# BW1092_USB.net
KiCad netlist of a schematic drawn in Altium Designer
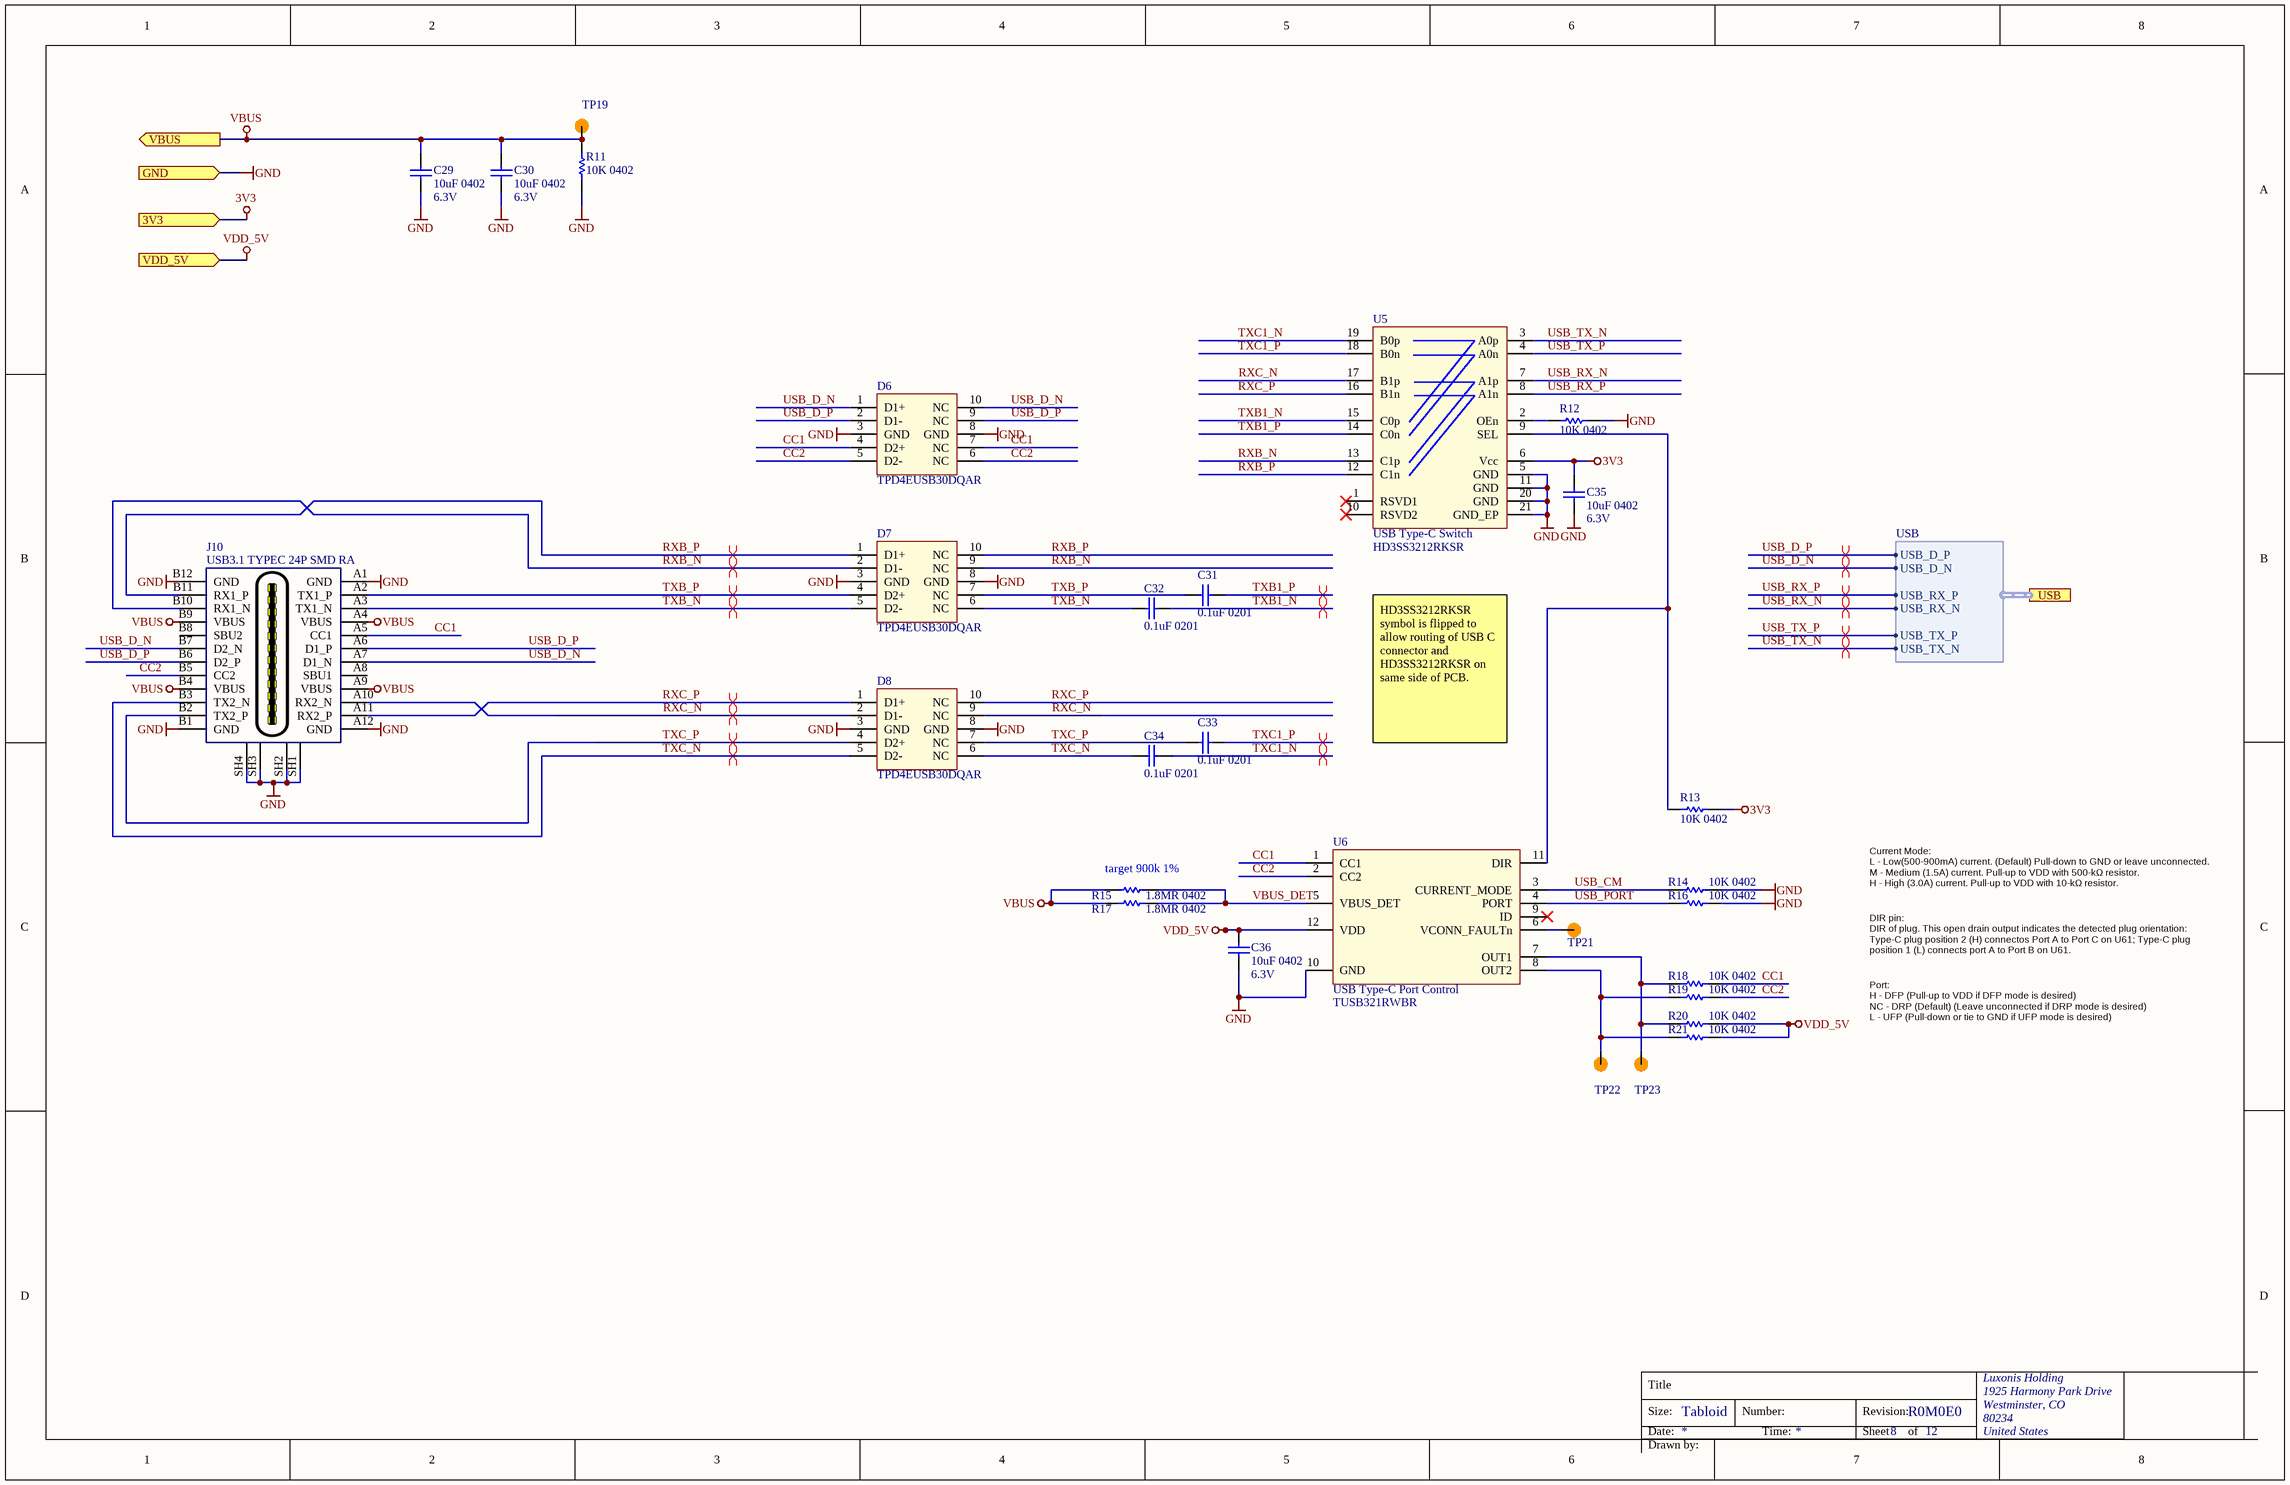
[diagram p0: BW1092_USB.SchDoc]

(export (version "E")
  (design (tool "Eeschema 10.0.6"))
  (components
    (comp (ref "C29")
      (value "10uF 0402")
      (footprint "CAP_Altium_Vault_Generic:CAPC0402(1005)70_L")
      (description "CAP CER 10UF 6.3V X5R 0402 20%")
      (fields (field (name "TOLERANCE") "20%") (field (name "VOLTAGE RATING") "6.3V"))
      (libsource (lib "LuxonisMaster") (part "GRM155R60J106ME15D"))
    )
    (comp (ref "C30")
      (value "10uF 0402")
      (footprint "CAP_Altium_Vault_Generic:CAPC0402(1005)70_L")
      (description "CAP CER 10UF 6.3V X5R 0402 20%")
      (fields (field (name "TOLERANCE") "20%") (field (name "VOLTAGE RATING") "6.3V"))
      (libsource (lib "LuxonisMaster") (part "GRM155R60J106ME15D"))
    )
    (comp (ref "C31")
      (value "0.1uF 0201")
      (footprint "CAP_Altium_Vault_Generic:CAPC0201(0603)33_L")
      (description "CAP CER 0.1UF 10V X5R 0201")
      (fields (field (name "TOLERANCE") "10%") (field (name "VOLTAGE") "10V"))
      (libsource (lib "LuxonisMaster") (part "GRM033R61A104KE15D"))
    )
    (comp (ref "C32")
      (value "0.1uF 0201")
      (footprint "CAP_Altium_Vault_Generic:CAPC0201(0603)33_L")
      (description "CAP CER 0.1UF 10V X5R 0201")
      (fields (field (name "TOLERANCE") "10%") (field (name "VOLTAGE") "10V"))
      (libsource (lib "LuxonisMaster") (part "GRM033R61A104KE15D"))
    )
    (comp (ref "C33")
      (value "0.1uF 0201")
      (footprint "CAP_Altium_Vault_Generic:CAPC0201(0603)33_L")
      (description "CAP CER 0.1UF 10V X5R 0201")
      (fields (field (name "TOLERANCE") "10%") (field (name "VOLTAGE") "10V"))
      (libsource (lib "LuxonisMaster") (part "GRM033R61A104KE15D"))
    )
    (comp (ref "C34")
      (value "0.1uF 0201")
      (footprint "CAP_Altium_Vault_Generic:CAPC0201(0603)33_L")
      (description "CAP CER 0.1UF 10V X5R 0201")
      (fields (field (name "TOLERANCE") "10%") (field (name "VOLTAGE") "10V"))
      (libsource (lib "LuxonisMaster") (part "GRM033R61A104KE15D"))
    )
    (comp (ref "C35")
      (value "10uF 0402")
      (footprint "CAP_Altium_Vault_Generic:CAPC0402(1005)70_L")
      (description "CAP CER 10UF 6.3V X5R 0402 20%")
      (fields (field (name "TOLERANCE") "20%") (field (name "VOLTAGE RATING") "6.3V"))
      (libsource (lib "LuxonisMaster") (part "GRM155R60J106ME15D"))
    )
    (comp (ref "C36")
      (value "10uF 0402")
      (footprint "CAP_Altium_Vault_Generic:CAPC0402(1005)70_L")
      (description "CAP CER 10UF 6.3V X5R 0402 20%")
      (fields (field (name "TOLERANCE") "20%") (field (name "VOLTAGE RATING") "6.3V"))
      (libsource (lib "LuxonisMaster") (part "GRM155R60J106ME15D"))
    )
    (comp (ref "D6")
      (value "TPD4EUSB30DQAR")
      (footprint "LuxonisMaster:TPD4EUSB30DQAR")
      (description "TVS DIODE 5.5V 8V 10SON 8V Clamp 1A (8/20µs) Ipp Tvs Diode Surface Mount 10-USON (2.5x1)")
      (libsource (lib "LuxonisMaster") (part "TPD4EUSB30DQAR"))
    )
    (comp (ref "D7")
      (value "TPD4EUSB30DQAR")
      (footprint "LuxonisMaster:TPD4EUSB30DQAR")
      (description "TVS DIODE 5.5V 8V 10SON 8V Clamp 1A (8/20µs) Ipp Tvs Diode Surface Mount 10-USON (2.5x1)")
      (libsource (lib "LuxonisMaster") (part "TPD4EUSB30DQAR"))
    )
    (comp (ref "D8")
      (value "TPD4EUSB30DQAR")
      (footprint "LuxonisMaster:TPD4EUSB30DQAR")
      (description "TVS DIODE 5.5V 8V 10SON 8V Clamp 1A (8/20µs) Ipp Tvs Diode Surface Mount 10-USON (2.5x1)")
      (libsource (lib "LuxonisMaster") (part "TPD4EUSB30DQAR"))
    )
    (comp (ref "J10")
      (value "USB3.1 TYPEC 24P SMD RA")
      (footprint "LuxonisMaster:105450-0101")
      (description "CONN RCP USB3.1 TYPEC 24P SMD RA")
      (libsource (lib "LuxonisMaster") (part "105450-0101"))
    )
    (comp (ref "R11")
      (value "10K 0402")
      (footprint "RES_Altium_Vault_Generic:RESC0402(1005)_L")
      (fields (field (name "TOLERANCE") "1%"))
      (libsource (lib "LuxonisMaster") (part "RC0402FR-1310KL"))
    )
    (comp (ref "R12")
      (value "10K 0402")
      (footprint "RES_Altium_Vault_Generic:RESC0402(1005)_L")
      (fields (field (name "TOLERANCE") "1%"))
      (libsource (lib "LuxonisMaster") (part "RC0402FR-1310KL"))
    )
    (comp (ref "R13")
      (value "10K 0402")
      (footprint "RES_Altium_Vault_Generic:RESC0402(1005)_L")
      (fields (field (name "TOLERANCE") "1%"))
      (libsource (lib "LuxonisMaster") (part "RC0402FR-1310KL"))
    )
    (comp (ref "R14")
      (value "10K 0402")
      (footprint "RES_Altium_Vault_Generic:RESC0402(1005)_L")
      (fields (field (name "TOLERANCE") "1%"))
      (libsource (lib "LuxonisMaster") (part "RC0402FR-1310KL"))
    )
    (comp (ref "R15")
      (value "1.8MR 0402")
      (footprint "RES_Altium_Vault_Generic:RESC0402(1005)_L")
      (description "RES SMD 1.8M OHM 1% 1/16W 0402")
      (fields (field (name "TOLERANCE") "1%"))
      (libsource (lib "LuxonisMaster") (part "CRCW04021M80FKED"))
    )
    (comp (ref "R16")
      (value "10K 0402")
      (footprint "RES_Altium_Vault_Generic:RESC0402(1005)_L")
      (fields (field (name "TOLERANCE") "1%"))
      (libsource (lib "LuxonisMaster") (part "RC0402FR-1310KL"))
    )
    (comp (ref "R17")
      (value "1.8MR 0402")
      (footprint "RES_Altium_Vault_Generic:RESC0402(1005)_L")
      (description "RES SMD 1.8M OHM 1% 1/16W 0402")
      (fields (field (name "TOLERANCE") "1%"))
      (libsource (lib "LuxonisMaster") (part "CRCW04021M80FKED"))
    )
    (comp (ref "R18")
      (value "10K 0402")
      (footprint "RES_Altium_Vault_Generic:RESC0402(1005)_L")
      (fields (field (name "TOLERANCE") "1%"))
      (libsource (lib "LuxonisMaster") (part "RC0402FR-1310KL"))
    )
    (comp (ref "R19")
      (value "10K 0402")
      (footprint "RES_Altium_Vault_Generic:RESC0402(1005)_L")
      (fields (field (name "TOLERANCE") "1%"))
      (libsource (lib "LuxonisMaster") (part "RC0402FR-1310KL"))
    )
    (comp (ref "R20")
      (value "10K 0402")
      (footprint "RES_Altium_Vault_Generic:RESC0402(1005)_L")
      (fields (field (name "TOLERANCE") "1%"))
      (libsource (lib "LuxonisMaster") (part "RC0402FR-1310KL"))
    )
    (comp (ref "R21")
      (value "10K 0402")
      (footprint "RES_Altium_Vault_Generic:RESC0402(1005)_L")
      (fields (field (name "TOLERANCE") "1%"))
      (libsource (lib "LuxonisMaster") (part "RC0402FR-1310KL"))
    )
    (comp (ref "TP19")
      (value "TP100_200_NS")
      (footprint "LuxonisMaster:TP100_200_NS")
      (libsource (lib "LuxonisMaster") (part "TEST_POINT"))
    )
    (comp (ref "TP21")
      (value "TP075_150_NS")
      (footprint "LuxonisMaster:TP075_150_NS")
      (libsource (lib "LuxonisMaster") (part "TEST_POINT"))
    )
    (comp (ref "TP22")
      (value "TP075_150_NS")
      (footprint "LuxonisMaster:TP075_150_NS")
      (libsource (lib "LuxonisMaster") (part "TEST_POINT"))
    )
    (comp (ref "TP23")
      (value "TP075_150_NS")
      (footprint "LuxonisMaster:TP075_150_NS")
      (libsource (lib "LuxonisMaster") (part "TEST_POINT"))
    )
    (comp (ref "U5")
      (value "USB Type-C Switch")
      (footprint "LuxonisMaster:HD3SS3212RKSR")
      (description "IC MUX 2:1 8 OHM 20VQFN")
      (fields (field (name "MANUFACTURER PART NUMBER 1") "HD3SS3212RKSR"))
      (libsource (lib "LuxonisMaster") (part "HD3SS3212RKSR"))
    )
    (comp (ref "U6")
      (value "USB Type-C Port Control")
      (footprint "LuxonisMaster:TUSB321RWBR")
      (description "IC USB PORT CONTROL TYPE-C 12X2Q")
      (fields (field (name "MANUFACTURER PART NUMBER 1") "TUSB321RWBR"))
      (libsource (lib "LuxonisMaster") (part "TUSB321RWBR"))
    )
  )
  (nets
    (net (code "2") (name "/CC1") (class "Default")
      (node (ref "D6") (pin "4") (pinfunction "D2+_4") (pintype "passive"))
      (node (ref "D6") (pin "7") (pinfunction "NC_7") (pintype "passive"))
      (node (ref "J10") (pin "A5") (pinfunction "CC1_A5") (pintype "passive"))
      (node (ref "R18") (pin "2") (pinfunction "2_2") (pintype "passive"))
      (node (ref "U6") (pin "1") (pinfunction "CC1_1") (pintype "passive"))
    )
    (net (code "3") (name "/CC2") (class "Default")
      (node (ref "D6") (pin "5") (pinfunction "D2-_5") (pintype "passive"))
      (node (ref "D6") (pin "6") (pinfunction "NC_6") (pintype "passive"))
      (node (ref "J10") (pin "B5") (pinfunction "CC2_B5") (pintype "passive"))
      (node (ref "R19") (pin "2") (pinfunction "2_2") (pintype "passive"))
      (node (ref "U6") (pin "2") (pinfunction "CC2_2") (pintype "passive"))
    )
    (net (code "4") (name "/RXB_N") (class "Default")
      (node (ref "D7") (pin "2") (pinfunction "D1-_2") (pintype "passive"))
      (node (ref "D7") (pin "9") (pinfunction "NC_9") (pintype "passive"))
      (node (ref "J10") (pin "B10") (pinfunction "RX1_N_B10") (pintype "passive"))
      (node (ref "U5") (pin "13") (pinfunction "C1p_13") (pintype "passive"))
    )
    (net (code "5") (name "/RXB_P") (class "Default")
      (node (ref "D7") (pin "1") (pinfunction "D1+_1") (pintype "passive"))
      (node (ref "D7") (pin "10") (pinfunction "NC_10") (pintype "passive"))
      (node (ref "J10") (pin "B11") (pinfunction "RX1_P_B11") (pintype "passive"))
      (node (ref "U5") (pin "12") (pinfunction "C1n_12") (pintype "passive"))
    )
    (net (code "6") (name "/RXC_N") (class "Default")
      (node (ref "D8") (pin "2") (pinfunction "D1-_2") (pintype "passive"))
      (node (ref "D8") (pin "9") (pinfunction "NC_9") (pintype "passive"))
      (node (ref "J10") (pin "A10") (pinfunction "RX2_N_A10") (pintype "passive"))
      (node (ref "U5") (pin "17") (pinfunction "B1p_17") (pintype "passive"))
    )
    (net (code "7") (name "/RXC_P") (class "Default")
      (node (ref "D8") (pin "1") (pinfunction "D1+_1") (pintype "passive"))
      (node (ref "D8") (pin "10") (pinfunction "NC_10") (pintype "passive"))
      (node (ref "J10") (pin "A11") (pinfunction "RX2_P_A11") (pintype "passive"))
      (node (ref "U5") (pin "16") (pinfunction "B1n_16") (pintype "passive"))
    )
    (net (code "8") (name "/TXB1_N") (class "Default")
      (node (ref "C32") (pin "2") (pinfunction "2_2") (pintype "passive"))
      (node (ref "U5") (pin "15") (pinfunction "C0p_15") (pintype "passive"))
    )
    (net (code "9") (name "/TXB1_P") (class "Default")
      (node (ref "C31") (pin "2") (pinfunction "2_2") (pintype "passive"))
      (node (ref "U5") (pin "14") (pinfunction "C0n_14") (pintype "passive"))
    )
    (net (code "10") (name "/TXB_N") (class "Default")
      (node (ref "C32") (pin "1") (pinfunction "1_1") (pintype "passive"))
      (node (ref "D7") (pin "5") (pinfunction "D2-_5") (pintype "passive"))
      (node (ref "D7") (pin "6") (pinfunction "NC_6") (pintype "passive"))
      (node (ref "J10") (pin "A3") (pinfunction "TX1_N_A3") (pintype "passive"))
    )
    (net (code "11") (name "/TXB_P") (class "Default")
      (node (ref "C31") (pin "1") (pinfunction "1_1") (pintype "passive"))
      (node (ref "D7") (pin "4") (pinfunction "D2+_4") (pintype "passive"))
      (node (ref "D7") (pin "7") (pinfunction "NC_7") (pintype "passive"))
      (node (ref "J10") (pin "A2") (pinfunction "TX1_P_A2") (pintype "passive"))
    )
    (net (code "12") (name "/TXC1_N") (class "Default")
      (node (ref "C34") (pin "2") (pinfunction "2_2") (pintype "passive"))
      (node (ref "U5") (pin "19") (pinfunction "B0p_19") (pintype "passive"))
    )
    (net (code "13") (name "/TXC1_P") (class "Default")
      (node (ref "C33") (pin "2") (pinfunction "2_2") (pintype "passive"))
      (node (ref "U5") (pin "18") (pinfunction "B0n_18") (pintype "passive"))
    )
    (net (code "14") (name "/TXC_N") (class "Default")
      (node (ref "C34") (pin "1") (pinfunction "1_1") (pintype "passive"))
      (node (ref "D8") (pin "5") (pinfunction "D2-_5") (pintype "passive"))
      (node (ref "D8") (pin "6") (pinfunction "NC_6") (pintype "passive"))
      (node (ref "J10") (pin "B3") (pinfunction "TX2_N_B3") (pintype "passive"))
    )
    (net (code "15") (name "/TXC_P") (class "Default")
      (node (ref "C33") (pin "1") (pinfunction "1_1") (pintype "passive"))
      (node (ref "D8") (pin "4") (pinfunction "D2+_4") (pintype "passive"))
      (node (ref "D8") (pin "7") (pinfunction "NC_7") (pintype "passive"))
      (node (ref "J10") (pin "B2") (pinfunction "TX2_P_B2") (pintype "passive"))
    )
    (net (code "16") (name "/USB_CM") (class "Default")
      (node (ref "R14") (pin "1") (pinfunction "1_1") (pintype "passive"))
      (node (ref "U6") (pin "3") (pinfunction "CURRENT_MODE_3") (pintype "passive"))
    )
    (net (code "17") (name "/USB_D_N") (class "Default")
      (node (ref "D6") (pin "1") (pinfunction "D1+_1") (pintype "passive"))
      (node (ref "D6") (pin "10") (pinfunction "NC_10") (pintype "passive"))
      (node (ref "J10") (pin "A7") (pinfunction "D1_N_A7") (pintype "passive"))
      (node (ref "J10") (pin "B7") (pinfunction "D2_N_B7") (pintype "passive"))
    )
    (net (code "18") (name "/USB_D_P") (class "Default")
      (node (ref "D6") (pin "2") (pinfunction "D1-_2") (pintype "passive"))
      (node (ref "D6") (pin "9") (pinfunction "NC_9") (pintype "passive"))
      (node (ref "J10") (pin "A6") (pinfunction "D1_P_A6") (pintype "passive"))
      (node (ref "J10") (pin "B6") (pinfunction "D2_P_B6") (pintype "passive"))
    )
    (net (code "19") (name "/USB_PORT") (class "Default")
      (node (ref "R16") (pin "1") (pinfunction "1_1") (pintype "passive"))
      (node (ref "U6") (pin "4") (pinfunction "PORT_4") (pintype "passive"))
    )
    (net (code "20") (name "/USB_RX_N") (class "Default")
      (node (ref "U5") (pin "7") (pinfunction "A1p_7") (pintype "passive"))
    )
    (net (code "21") (name "/USB_RX_P") (class "Default")
      (node (ref "U5") (pin "8") (pinfunction "A1n_8") (pintype "passive"))
    )
    (net (code "22") (name "/USB_TX_N") (class "Default")
      (node (ref "U5") (pin "3") (pinfunction "A0p_3") (pintype "passive"))
    )
    (net (code "23") (name "/USB_TX_P") (class "Default")
      (node (ref "U5") (pin "4") (pinfunction "A0n_4") (pintype "passive"))
    )
    (net (code "24") (name "/VBUS_DET") (class "Default")
      (node (ref "R15") (pin "2") (pinfunction "2_2") (pintype "passive"))
      (node (ref "R17") (pin "2") (pinfunction "2_2") (pintype "passive"))
      (node (ref "U6") (pin "5") (pinfunction "VBUS_DET_5") (pintype "passive"))
    )
    (net (code "26") (name "3V3") (class "Default")
      (node (ref "C35") (pin "2") (pinfunction "2_2") (pintype "passive"))
      (node (ref "R13") (pin "2") (pinfunction "2_2") (pintype "passive"))
      (node (ref "U5") (pin "6") (pinfunction "Vcc_6") (pintype "passive"))
    )
    (net (code "27") (name "GND") (class "Default")
      (node (ref "C29") (pin "1") (pinfunction "1_1") (pintype "passive"))
      (node (ref "C30") (pin "1") (pinfunction "1_1") (pintype "passive"))
      (node (ref "C35") (pin "1") (pinfunction "1_1") (pintype "passive"))
      (node (ref "C36") (pin "1") (pinfunction "1_1") (pintype "passive"))
      (node (ref "D6") (pin "3") (pinfunction "GND_3") (pintype "passive"))
      (node (ref "D6") (pin "8") (pinfunction "GND_8") (pintype "passive"))
      (node (ref "D7") (pin "3") (pinfunction "GND_3") (pintype "passive"))
      (node (ref "D7") (pin "8") (pinfunction "GND_8") (pintype "passive"))
      (node (ref "D8") (pin "3") (pinfunction "GND_3") (pintype "passive"))
      (node (ref "D8") (pin "8") (pinfunction "GND_8") (pintype "passive"))
      (node (ref "J10") (pin "A1") (pinfunction "GND_A1") (pintype "passive"))
      (node (ref "J10") (pin "A12") (pinfunction "GND_A12") (pintype "passive"))
      (node (ref "J10") (pin "B1") (pinfunction "GND_B1") (pintype "passive"))
      (node (ref "J10") (pin "B12") (pinfunction "GND_B12") (pintype "passive"))
      (node (ref "J10") (pin "SH1") (pinfunction "SH_SH1") (pintype "passive"))
      (node (ref "J10") (pin "SH2") (pinfunction "SH_SH2") (pintype "passive"))
      (node (ref "J10") (pin "SH3") (pinfunction "SH_SH3") (pintype "passive"))
      (node (ref "J10") (pin "SH4") (pinfunction "SH_SH4") (pintype "passive"))
      (node (ref "R11") (pin "1") (pinfunction "1_1") (pintype "passive"))
      (node (ref "R12") (pin "2") (pinfunction "2_2") (pintype "passive"))
      (node (ref "R14") (pin "2") (pinfunction "2_2") (pintype "passive"))
      (node (ref "R16") (pin "2") (pinfunction "2_2") (pintype "passive"))
      (node (ref "U5") (pin "11") (pinfunction "GND_11") (pintype "passive"))
      (node (ref "U5") (pin "20") (pinfunction "GND_20") (pintype "passive"))
      (node (ref "U5") (pin "21") (pinfunction "GND_EP_21") (pintype "passive"))
      (node (ref "U5") (pin "5") (pinfunction "GND_5") (pintype "passive"))
      (node (ref "U6") (pin "10") (pinfunction "GND_10") (pintype "passive"))
    )
    (net (code "28") (name "Net-(U5-OEn)") (class "Default")
      (node (ref "R12") (pin "1") (pinfunction "1_1") (pintype "passive"))
      (node (ref "U5") (pin "2") (pinfunction "OEn_2") (pintype "passive"))
    )
    (net (code "29") (name "Net-(U5-SEL)") (class "Default")
      (node (ref "R13") (pin "1") (pinfunction "1_1") (pintype "passive"))
      (node (ref "U5") (pin "9") (pinfunction "SEL_9") (pintype "passive"))
      (node (ref "U6") (pin "11") (pinfunction "DIR_11") (pintype "passive"))
    )
    (net (code "30") (name "Net-(U6-OUT1)") (class "Default")
      (node (ref "R18") (pin "1") (pinfunction "1_1") (pintype "passive"))
      (node (ref "R20") (pin "1") (pinfunction "1_1") (pintype "passive"))
      (node (ref "TP23") (pin "1") (pintype "passive"))
      (node (ref "U6") (pin "7") (pinfunction "OUT1_7") (pintype "passive"))
    )
    (net (code "31") (name "Net-(U6-OUT2)") (class "Default")
      (node (ref "R19") (pin "1") (pinfunction "1_1") (pintype "passive"))
      (node (ref "R21") (pin "1") (pinfunction "1_1") (pintype "passive"))
      (node (ref "TP22") (pin "1") (pintype "passive"))
      (node (ref "U6") (pin "8") (pinfunction "OUT2_8") (pintype "passive"))
    )
    (net (code "32") (name "Net-(U6-VCONN_FAULTn)") (class "Default")
      (node (ref "TP21") (pin "1") (pintype "passive"))
      (node (ref "U6") (pin "6") (pinfunction "VCONN_FAULTn_6") (pintype "passive"))
    )
    (net (code "33") (name "VBUS") (class "Default")
      (node (ref "C29") (pin "2") (pinfunction "2_2") (pintype "passive"))
      (node (ref "C30") (pin "2") (pinfunction "2_2") (pintype "passive"))
      (node (ref "J10") (pin "A4") (pinfunction "VBUS_A4") (pintype "passive"))
      (node (ref "J10") (pin "A9") (pinfunction "VBUS_A9") (pintype "passive"))
      (node (ref "J10") (pin "B4") (pinfunction "VBUS_B4") (pintype "passive"))
      (node (ref "J10") (pin "B9") (pinfunction "VBUS_B9") (pintype "passive"))
      (node (ref "R11") (pin "2") (pinfunction "2_2") (pintype "passive"))
      (node (ref "R15") (pin "1") (pinfunction "1_1") (pintype "passive"))
      (node (ref "R17") (pin "1") (pinfunction "1_1") (pintype "passive"))
      (node (ref "TP19") (pin "1") (pintype "passive"))
    )
    (net (code "34") (name "VDD_5V") (class "Default")
      (node (ref "C36") (pin "2") (pinfunction "2_2") (pintype "passive"))
      (node (ref "R20") (pin "2") (pinfunction "2_2") (pintype "passive"))
      (node (ref "R21") (pin "2") (pinfunction "2_2") (pintype "passive"))
      (node (ref "U6") (pin "12") (pinfunction "VDD_12") (pintype "passive"))
    )
    (net (code "35") (name "unconnected-(J10-SBU1-PadA8)") (class "Default")
      (node (ref "J10") (pin "A8") (pinfunction "SBU1_A8") (pintype "passive"))
    )
    (net (code "36") (name "unconnected-(J10-SBU2-PadB8)") (class "Default")
      (node (ref "J10") (pin "B8") (pinfunction "SBU2_B8") (pintype "passive"))
    )
    (net (code "37") (name "unconnected-(U5-RSVD1-Pad1)") (class "Default")
      (node (ref "U5") (pin "1") (pinfunction "RSVD1_1") (pintype "passive+no_connect"))
    )
    (net (code "38") (name "unconnected-(U5-RSVD2-Pad10)") (class "Default")
      (node (ref "U5") (pin "10") (pinfunction "RSVD2_10") (pintype "passive+no_connect"))
    )
    (net (code "39") (name "unconnected-(U6-ID-Pad9)") (class "Default")
      (node (ref "U6") (pin "9") (pinfunction "ID_9") (pintype "passive+no_connect"))
    )
  )
)
